# test.net
KiCad netlist of a schematic drawn in Altium Designer
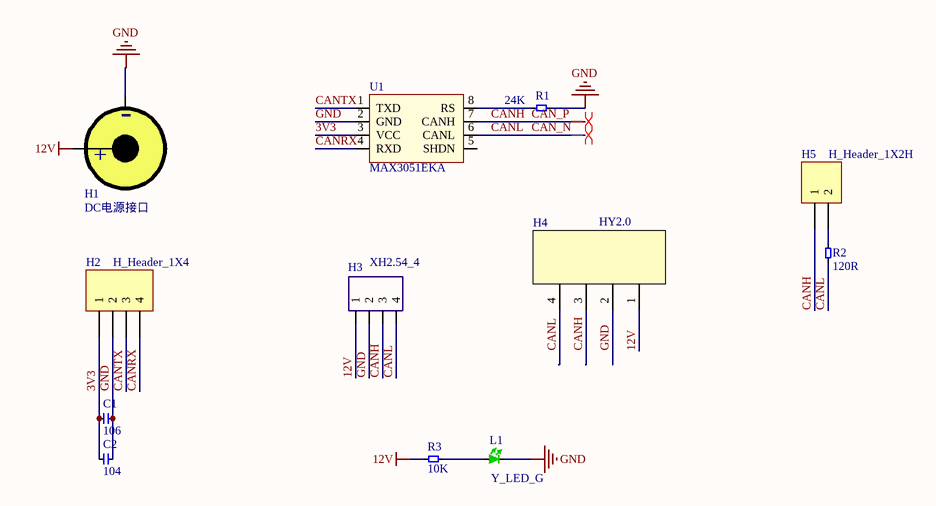
[diagram p0: test.SchDoc]

(export (version "E")
  (design (tool "Eeschema 10.0.6"))
  (components
    (comp (ref "C1")
      (value "106")
      (footprint "C_0603")
      (description "无极性贴片电容")
      (libsource (lib "电阻电容电感库") (part "C_无极贴片"))
    )
    (comp (ref "C2")
      (value "104")
      (footprint "C_0603")
      (description "无极性贴片电容")
      (libsource (lib "电阻电容电感库") (part "C_无极贴片"))
    )
    (comp (ref "H1") (value "DC电源接口") (footprint "DC005-插件") (libsource (lib "接插件") (part "DC电源接口")))
    (comp (ref "H2")
      (value "H_Header_1X4")
      (footprint "H_Header_1X4")
      (description "单排4针排针")
      (fields (field (name "PUBLISHER") "Altium Limited"))
      (libsource (lib "接插件") (part "H_Header_1X4"))
    )
    (comp (ref "H3")
      (value "XH2.54_4")
      (footprint "H_XH2.54_4")
      (description "4脚小白头")
      (fields (field (name "PUBLISHER") "Altium Limited"))
      (libsource (lib "接插件") (part "H_XH2.54_4"))
    )
    (comp (ref "H4")
      (value "HY2.0")
      (footprint "HY2.0_4P_插直 - duplicate")
      (libsource (lib "端子") (part "HY2.0_4P"))
    )
    (comp (ref "H5")
      (value "H_Header_1X2H")
      (footprint "H_Header_1X2")
      (description "单排2针排母")
      (fields (field (name "PUBLISHER") "Altium Limited"))
      (libsource (lib "接插件") (part "H_Header_1X2H"))
    )
    (comp (ref "L1")
      (value "Y_LED_G")
      (footprint "Y_LED_0603_G")
      (description "绿色LED")
      (libsource (lib "声光元件") (part "Y_LED_G"))
    )
    (comp (ref "R1")
      (value "24K")
      (footprint "R_0603")
      (description "贴片电阻")
      (libsource (lib "电阻电容电感库") (part "R_贴片"))
    )
    (comp (ref "R2")
      (value "120R")
      (footprint "R_0603")
      (description "贴片电阻")
      (libsource (lib "电阻电容电感库") (part "R_贴片"))
    )
    (comp (ref "R3")
      (value "10K")
      (footprint "R_0603")
      (description "贴片电阻")
      (libsource (lib "电阻电容电感库") (part "R_贴片"))
    )
    (comp (ref "U1")
      (value "MAX3051EKA")
      (footprint "SOT23-8")
      (description "CAN-1Mbps")
      (libsource (lib "物流小车-pcb-树莓派") (part "MAX3051EKA"))
    )
  )
  (nets
    (net (code "1") (name "/3V3") (class "Default")
      (node (ref "C1") (pin "1") (pinfunction "1_1") (pintype "passive"))
      (node (ref "C2") (pin "1") (pinfunction "1_1") (pintype "passive"))
      (node (ref "H2") (pin "1") (pinfunction "1_1") (pintype "passive"))
      (node (ref "U1") (pin "3") (pinfunction "VCC_3") (pintype "passive"))
    )
    (net (code "2") (name "/CANH") (class "Default")
      (node (ref "H3") (pin "3") (pinfunction "3_3") (pintype "passive"))
      (node (ref "H4") (pin "3") (pintype "passive"))
      (node (ref "H5") (pin "1") (pinfunction "1_1") (pintype "passive"))
      (node (ref "U1") (pin "7") (pinfunction "CANH_7") (pintype "passive"))
    )
    (net (code "3") (name "/CANL") (class "Default")
      (node (ref "H3") (pin "4") (pinfunction "4_4") (pintype "passive"))
      (node (ref "H4") (pin "4") (pintype "passive"))
      (node (ref "R2") (pin "1") (pintype "passive"))
      (node (ref "U1") (pin "6") (pinfunction "CANL_6") (pintype "passive"))
    )
    (net (code "4") (name "/CANRX") (class "Default")
      (node (ref "H2") (pin "4") (pinfunction "4_4") (pintype "passive"))
      (node (ref "U1") (pin "4") (pinfunction "RXD_4") (pintype "passive"))
    )
    (net (code "5") (name "/CANTX") (class "Default")
      (node (ref "H2") (pin "3") (pinfunction "3_3") (pintype "passive"))
      (node (ref "U1") (pin "1") (pinfunction "TXD_1") (pintype "passive"))
    )
    (net (code "6") (name "12V") (class "Default")
      (node (ref "H1") (pin "2") (pinfunction "2_2") (pintype "passive"))
      (node (ref "H3") (pin "1") (pinfunction "1_1") (pintype "passive"))
      (node (ref "H4") (pin "1") (pintype "passive"))
      (node (ref "R3") (pin "1") (pintype "passive"))
    )
    (net (code "7") (name "GND") (class "Default")
      (node (ref "C1") (pin "2") (pinfunction "2_2") (pintype "passive"))
      (node (ref "C2") (pin "2") (pinfunction "2_2") (pintype "passive"))
      (node (ref "H1") (pin "1") (pintype "passive"))
      (node (ref "H2") (pin "2") (pinfunction "2_2") (pintype "passive"))
      (node (ref "H3") (pin "2") (pinfunction "2_2") (pintype "passive"))
      (node (ref "H4") (pin "2") (pintype "passive"))
      (node (ref "L1") (pin "2") (pintype "passive"))
      (node (ref "R1") (pin "1") (pintype "passive"))
      (node (ref "U1") (pin "2") (pinfunction "GND_2") (pintype "passive"))
    )
    (net (code "8") (name "Net-(H5-Pad2)") (class "Default")
      (node (ref "H5") (pin "2") (pinfunction "2_2") (pintype "passive"))
      (node (ref "R2") (pin "2") (pintype "passive"))
    )
    (net (code "9") (name "Net-(L1-Pad1)") (class "Default")
      (node (ref "L1") (pin "1") (pintype "passive"))
      (node (ref "R3") (pin "2") (pintype "passive"))
    )
    (net (code "10") (name "Net-(U1-RS)") (class "Default")
      (node (ref "R1") (pin "2") (pintype "passive"))
      (node (ref "U1") (pin "8") (pinfunction "RS_8") (pintype "passive"))
    )
    (net (code "11") (name "unconnected-(U1-SHDN-Pad5)") (class "Default")
      (node (ref "U1") (pin "5") (pinfunction "SHDN_5") (pintype "passive"))
    )
  )
)
